# ESP32_Metal_Detector_v1_0.net
KiCad netlist of a schematic drawn in EAGLE
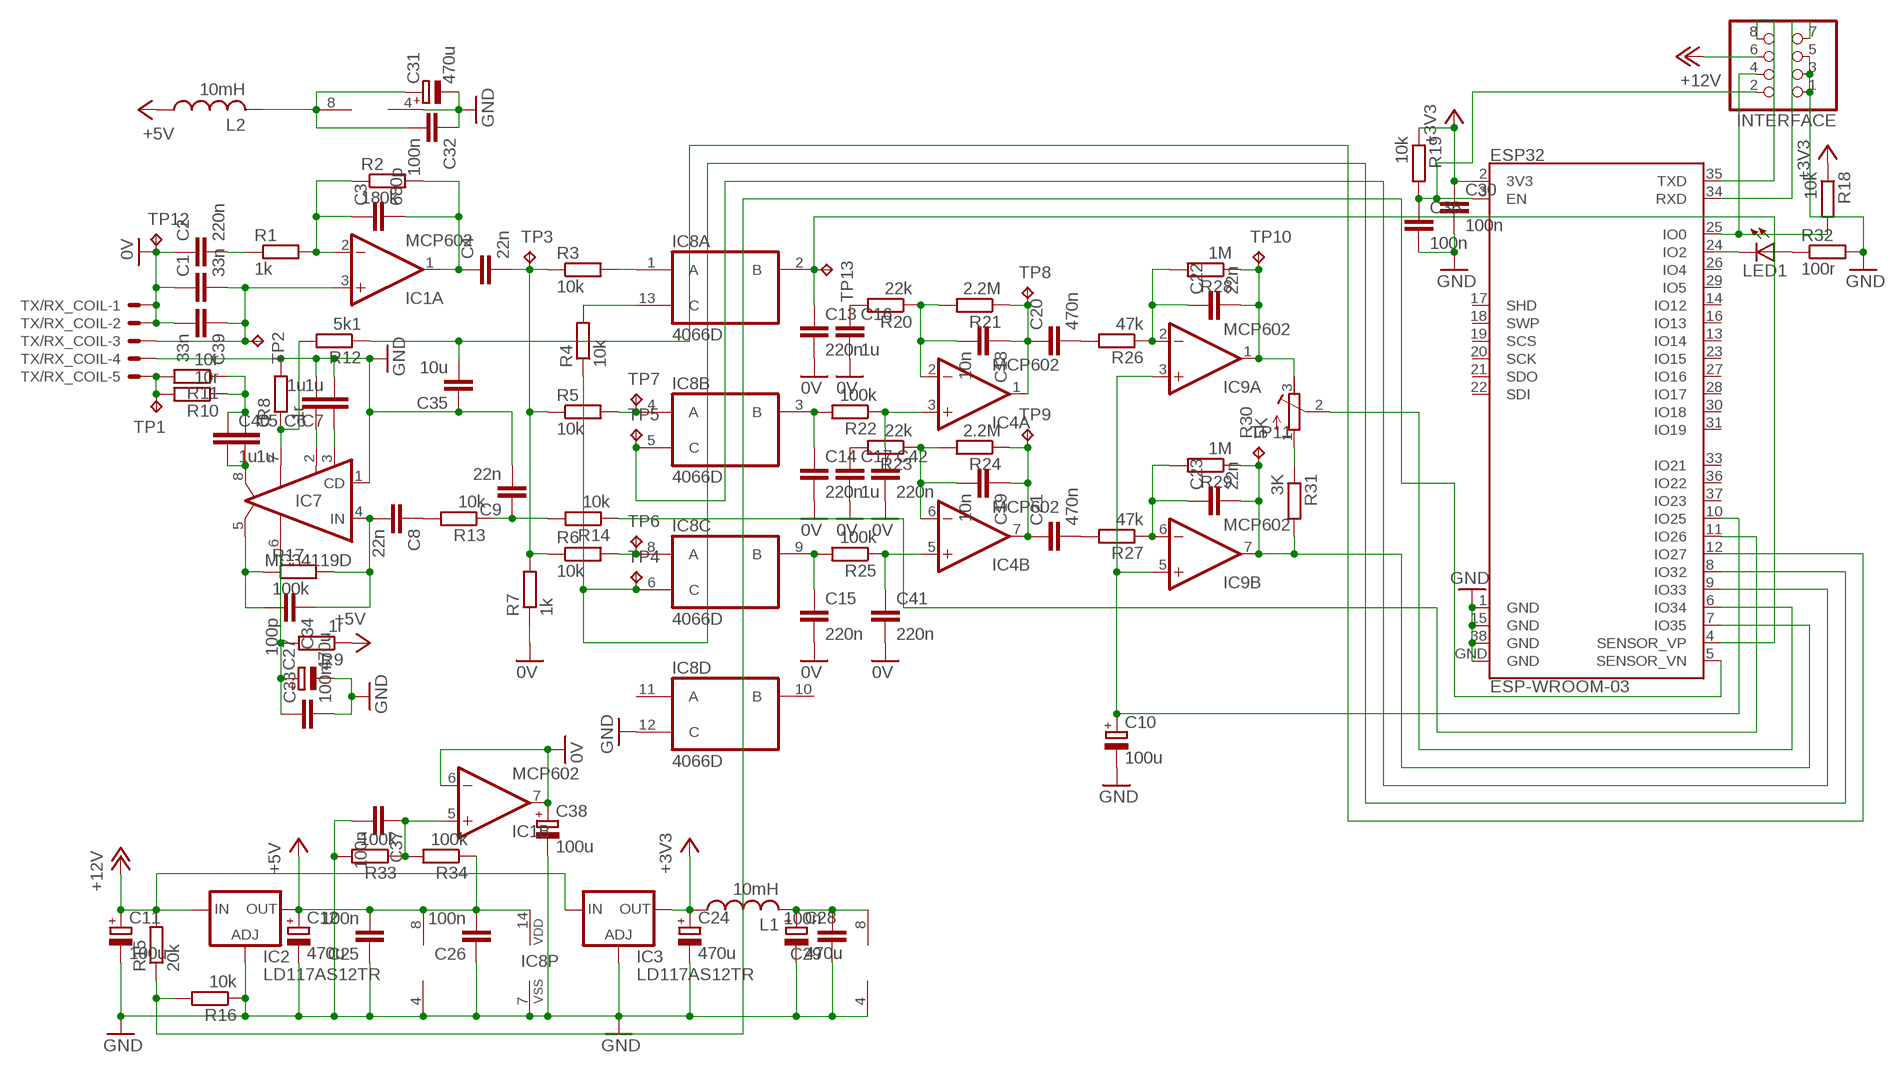
[diagram p0: schematic, sheet 1]

(export (version "E")
  (design (tool "Eeschema 10.0.6"))
  (components
    (comp (ref "C1")
      (value "33n")
      (footprint "eagle-import:C050-055X075")
      (libsource (lib "eagle-import") (part "C-EU050-055X075"))
    )
    (comp (ref "C2")
      (value "220n")
      (footprint "eagle-import:C1206")
      (libsource (lib "eagle-import") (part "resistor_C-EUC1206"))
    )
    (comp (ref "C3")
      (value "680p")
      (footprint "eagle-import:C1206")
      (libsource (lib "eagle-import") (part "resistor_C-EUC1206"))
    )
    (comp (ref "C4")
      (value "22n")
      (footprint "eagle-import:C1206")
      (libsource (lib "eagle-import") (part "resistor_C-EUC1206"))
    )
    (comp (ref "C5")
      (value "1u")
      (footprint "eagle-import:C050-055X075")
      (libsource (lib "eagle-import") (part "C-EU050-055X075"))
    )
    (comp (ref "C6")
      (value "1u")
      (footprint "eagle-import:C1206")
      (libsource (lib "eagle-import") (part "resistor_C-EUC1206"))
    )
    (comp (ref "C7")
      (value "1u")
      (footprint "eagle-import:C1206")
      (libsource (lib "eagle-import") (part "resistor_C-EUC1206"))
    )
    (comp (ref "C8")
      (value "22n")
      (footprint "eagle-import:C1206")
      (libsource (lib "eagle-import") (part "resistor_C-EUC1206"))
    )
    (comp (ref "C9")
      (value "22n")
      (footprint "eagle-import:C1206")
      (libsource (lib "eagle-import") (part "resistor_C-EUC1206"))
    )
    (comp (ref "C10")
      (value "100u")
      (footprint "eagle-import:SMC_B")
      (libsource (lib "eagle-import") (part "CPOL-EUSMCB"))
    )
    (comp (ref "C11")
      (value "100u")
      (footprint "eagle-import:SMC_E")
      (libsource (lib "eagle-import") (part "CPOL-EUSMCE"))
    )
    (comp (ref "C12")
      (value "470u")
      (footprint "eagle-import:SMC_D")
      (libsource (lib "eagle-import") (part "CPOL-EUSMCD"))
    )
    (comp (ref "C13")
      (value "220n")
      (footprint "eagle-import:C1206")
      (libsource (lib "eagle-import") (part "resistor_C-EUC1206"))
    )
    (comp (ref "C14")
      (value "220n")
      (footprint "eagle-import:C1206")
      (libsource (lib "eagle-import") (part "resistor_C-EUC1206"))
    )
    (comp (ref "C15")
      (value "220n")
      (footprint "eagle-import:C1206")
      (libsource (lib "eagle-import") (part "resistor_C-EUC1206"))
    )
    (comp (ref "C16")
      (value "1u")
      (footprint "eagle-import:C1206")
      (libsource (lib "eagle-import") (part "resistor_C-EUC1206"))
    )
    (comp (ref "C17")
      (value "1u")
      (footprint "eagle-import:C1206")
      (libsource (lib "eagle-import") (part "resistor_C-EUC1206"))
    )
    (comp (ref "C18")
      (value "10n")
      (footprint "eagle-import:C1206")
      (libsource (lib "eagle-import") (part "resistor_C-EUC1206"))
    )
    (comp (ref "C19")
      (value "10n")
      (footprint "eagle-import:C1206")
      (libsource (lib "eagle-import") (part "resistor_C-EUC1206"))
    )
    (comp (ref "C20")
      (value "470n")
      (footprint "eagle-import:C1206")
      (libsource (lib "eagle-import") (part "resistor_C-EUC1206"))
    )
    (comp (ref "C21")
      (value "470n")
      (footprint "eagle-import:C1206")
      (libsource (lib "eagle-import") (part "resistor_C-EUC1206"))
    )
    (comp (ref "C22")
      (value "22n")
      (footprint "eagle-import:C1206")
      (libsource (lib "eagle-import") (part "resistor_C-EUC1206"))
    )
    (comp (ref "C23")
      (value "22n")
      (footprint "eagle-import:C1206")
      (libsource (lib "eagle-import") (part "resistor_C-EUC1206"))
    )
    (comp (ref "C24")
      (value "470u")
      (footprint "eagle-import:SMC_D")
      (libsource (lib "eagle-import") (part "CPOL-EUSMCD"))
    )
    (comp (ref "C25")
      (value "100n")
      (footprint "eagle-import:C1206")
      (libsource (lib "eagle-import") (part "resistor_C-EUC1206"))
    )
    (comp (ref "C26")
      (value "100n")
      (footprint "eagle-import:C1206")
      (libsource (lib "eagle-import") (part "resistor_C-EUC1206"))
    )
    (comp (ref "C27")
      (value "470u")
      (footprint "eagle-import:SMC_D")
      (libsource (lib "eagle-import") (part "CPOL-EUSMCD"))
    )
    (comp (ref "C28")
      (value "470u")
      (footprint "eagle-import:SMC_D")
      (libsource (lib "eagle-import") (part "CPOL-EUSMCD"))
    )
    (comp (ref "C29")
      (value "100n")
      (footprint "eagle-import:C1206")
      (libsource (lib "eagle-import") (part "resistor_C-EUC1206"))
    )
    (comp (ref "C30")
      (value "100n")
      (footprint "eagle-import:C1206")
      (libsource (lib "eagle-import") (part "resistor_C-EUC1206"))
    )
    (comp (ref "C31")
      (value "470u")
      (footprint "eagle-import:SMC_D")
      (libsource (lib "eagle-import") (part "CPOL-EUSMCD"))
    )
    (comp (ref "C32")
      (value "100n")
      (footprint "eagle-import:C1206")
      (libsource (lib "eagle-import") (part "resistor_C-EUC1206"))
    )
    (comp (ref "C33")
      (value "100n")
      (footprint "eagle-import:C1206")
      (libsource (lib "eagle-import") (part "resistor_C-EUC1206"))
    )
    (comp (ref "C34")
      (value "100p")
      (footprint "eagle-import:C1206")
      (libsource (lib "eagle-import") (part "resistor_C-EUC1206"))
    )
    (comp (ref "C35")
      (value "10u")
      (footprint "eagle-import:C1206")
      (libsource (lib "eagle-import") (part "resistor_C-EUC1206"))
    )
    (comp (ref "C36")
      (value "100n")
      (footprint "eagle-import:C1206")
      (libsource (lib "eagle-import") (part "resistor_C-EUC1206"))
    )
    (comp (ref "C37")
      (value "100n")
      (footprint "eagle-import:C1206")
      (libsource (lib "eagle-import") (part "resistor_C-EUC1206"))
    )
    (comp (ref "C38")
      (value "100u")
      (footprint "eagle-import:SMC_B")
      (libsource (lib "eagle-import") (part "CPOL-EUSMCB"))
    )
    (comp (ref "C39")
      (value "33n")
      (footprint "eagle-import:C1206")
      (libsource (lib "eagle-import") (part "resistor_C-EUC1206"))
    )
    (comp (ref "C40")
      (value "1u")
      (footprint "eagle-import:C1206")
      (libsource (lib "eagle-import") (part "resistor_C-EUC1206"))
    )
    (comp (ref "C41")
      (value "220n")
      (footprint "eagle-import:C1206")
      (libsource (lib "eagle-import") (part "resistor_C-EUC1206"))
    )
    (comp (ref "C42")
      (value "220n")
      (footprint "eagle-import:C1206")
      (libsource (lib "eagle-import") (part "resistor_C-EUC1206"))
    )
    (comp (ref "ESP32")
      (value "ESP-WROOM-03")
      (footprint "eagle-import:ESP-WROOM-03")
      (libsource (lib "eagle-import") (part "ESP-WROOM-03"))
    )
    (comp (ref "IC1")
      (value "MCP602")
      (footprint "eagle-import:SO08")
      (libsource (lib "eagle-import") (part "LM393D"))
    )
    (comp (ref "IC2")
      (value "LD117AS12TR")
      (footprint "eagle-import:SOT223")
      (libsource (lib "eagle-import") (part "LD117A?S12TR"))
    )
    (comp (ref "IC3")
      (value "LD117AS12TR")
      (footprint "eagle-import:SOT223")
      (libsource (lib "eagle-import") (part "LD117A?S12TR"))
    )
    (comp (ref "IC4")
      (value "MCP602")
      (footprint "eagle-import:SO08")
      (libsource (lib "eagle-import") (part "LM393D"))
    )
    (comp (ref "IC7")
      (value "MC34119D")
      (footprint "eagle-import:SO08")
      (libsource (lib "eagle-import") (part "MC34119D"))
    )
    (comp (ref "IC8")
      (value "4066D")
      (footprint "eagle-import:SO14")
      (libsource (lib "eagle-import") (part "4066D"))
    )
    (comp (ref "IC9")
      (value "MCP602")
      (footprint "eagle-import:SO08")
      (libsource (lib "eagle-import") (part "LM393D"))
    )
    (comp (ref "INTERFACE")
      (value "PINHD-2X4")
      (footprint "eagle-import:2X04")
      (libsource (lib "eagle-import") (part "PINHD-2X4"))
    )
    (comp (ref "L1")
      (value "10mH")
      (footprint "eagle-import:L5650M")
      (libsource (lib "eagle-import") (part "L-USL5650M"))
    )
    (comp (ref "L2")
      (value "10mH")
      (footprint "eagle-import:L5650M")
      (libsource (lib "eagle-import") (part "L-USL5650M"))
    )
    (comp (ref "LED1")
      (value "LEDSML1206")
      (footprint "eagle-import:SML1206")
      (libsource (lib "eagle-import") (part "LEDSML1206"))
    )
    (comp (ref "R1")
      (value "1k")
      (footprint "eagle-import:R1206")
      (libsource (lib "eagle-import") (part "R-EU_R1206"))
    )
    (comp (ref "R2")
      (value "180k")
      (footprint "eagle-import:R1206")
      (libsource (lib "eagle-import") (part "R-EU_R1206"))
    )
    (comp (ref "R3")
      (value "10k")
      (footprint "eagle-import:R1206")
      (libsource (lib "eagle-import") (part "R-EU_R1206"))
    )
    (comp (ref "R4")
      (value "10k")
      (footprint "eagle-import:R1206")
      (libsource (lib "eagle-import") (part "R-EU_R1206"))
    )
    (comp (ref "R5")
      (value "10k")
      (footprint "eagle-import:R1206")
      (libsource (lib "eagle-import") (part "R-EU_R1206"))
    )
    (comp (ref "R6")
      (value "10k")
      (footprint "eagle-import:R1206")
      (libsource (lib "eagle-import") (part "R-EU_R1206"))
    )
    (comp (ref "R7")
      (value "1k")
      (footprint "eagle-import:R1206")
      (libsource (lib "eagle-import") (part "R-EU_R1206"))
    )
    (comp (ref "R8")
      (value "1r")
      (footprint "eagle-import:R1206")
      (libsource (lib "eagle-import") (part "R-EU_R1206"))
    )
    (comp (ref "R9")
      (value "1r")
      (footprint "eagle-import:R1206")
      (libsource (lib "eagle-import") (part "R-EU_R1206"))
    )
    (comp (ref "R10")
      (value "10r")
      (footprint "eagle-import:R1206")
      (libsource (lib "eagle-import") (part "R-EU_R1206"))
    )
    (comp (ref "R11")
      (value "10r")
      (footprint "eagle-import:R1206")
      (libsource (lib "eagle-import") (part "R-EU_R1206"))
    )
    (comp (ref "R12")
      (value "5k1")
      (footprint "eagle-import:R1206")
      (libsource (lib "eagle-import") (part "R-EU_R1206"))
    )
    (comp (ref "R13")
      (value "10k")
      (footprint "eagle-import:R1206")
      (libsource (lib "eagle-import") (part "R-EU_R1206"))
    )
    (comp (ref "R14")
      (value "10k")
      (footprint "eagle-import:R1206")
      (libsource (lib "eagle-import") (part "R-EU_R1206"))
    )
    (comp (ref "R15")
      (value "20k")
      (footprint "eagle-import:R1206")
      (libsource (lib "eagle-import") (part "R-EU_R1206"))
    )
    (comp (ref "R16")
      (value "10k")
      (footprint "eagle-import:R1206")
      (libsource (lib "eagle-import") (part "R-EU_R1206"))
    )
    (comp (ref "R17")
      (value "100k")
      (footprint "eagle-import:R1206")
      (libsource (lib "eagle-import") (part "R-EU_R1206"))
    )
    (comp (ref "R18")
      (value "10k")
      (footprint "eagle-import:R1206")
      (libsource (lib "eagle-import") (part "R-EU_R1206"))
    )
    (comp (ref "R19")
      (value "10k")
      (footprint "eagle-import:R1206")
      (libsource (lib "eagle-import") (part "R-EU_R1206"))
    )
    (comp (ref "R20")
      (value "22k")
      (footprint "eagle-import:R1206")
      (libsource (lib "eagle-import") (part "R-EU_R1206"))
    )
    (comp (ref "R21")
      (value "2.2M")
      (footprint "eagle-import:R1206")
      (libsource (lib "eagle-import") (part "R-EU_R1206"))
    )
    (comp (ref "R22")
      (value "100k")
      (footprint "eagle-import:R1206")
      (libsource (lib "eagle-import") (part "R-EU_R1206"))
    )
    (comp (ref "R23")
      (value "22k")
      (footprint "eagle-import:R1206")
      (libsource (lib "eagle-import") (part "R-EU_R1206"))
    )
    (comp (ref "R24")
      (value "2.2M")
      (footprint "eagle-import:R1206")
      (libsource (lib "eagle-import") (part "R-EU_R1206"))
    )
    (comp (ref "R25")
      (value "100k")
      (footprint "eagle-import:R1206")
      (libsource (lib "eagle-import") (part "R-EU_R1206"))
    )
    (comp (ref "R26")
      (value "47k")
      (footprint "eagle-import:R1206")
      (libsource (lib "eagle-import") (part "R-EU_R1206"))
    )
    (comp (ref "R27")
      (value "47k")
      (footprint "eagle-import:R1206")
      (libsource (lib "eagle-import") (part "R-EU_R1206"))
    )
    (comp (ref "R28")
      (value "1M")
      (footprint "eagle-import:R1206")
      (libsource (lib "eagle-import") (part "R-EU_R1206"))
    )
    (comp (ref "R29")
      (value "1M")
      (footprint "eagle-import:R1206")
      (libsource (lib "eagle-import") (part "R-EU_R1206"))
    )
    (comp (ref "R30")
      (value "5K")
      (footprint "eagle-import:RTRIM4G_J")
      (libsource (lib "eagle-import") (part "R-TRIMM4G/J"))
    )
    (comp (ref "R31")
      (value "3K")
      (footprint "eagle-import:R1206")
      (libsource (lib "eagle-import") (part "R-EU_R1206"))
    )
    (comp (ref "R32")
      (value "100r")
      (footprint "eagle-import:R1206")
      (libsource (lib "eagle-import") (part "R-EU_R1206"))
    )
    (comp (ref "R33")
      (value "100k")
      (footprint "eagle-import:R1206")
      (libsource (lib "eagle-import") (part "R-EU_R1206"))
    )
    (comp (ref "R34")
      (value "100k")
      (footprint "eagle-import:R1206")
      (libsource (lib "eagle-import") (part "R-EU_R1206"))
    )
    (comp (ref "TP1")
      (value "TPPAD1-13")
      (footprint "eagle-import:P1-13")
      (libsource (lib "eagle-import") (part "TPPAD1-13"))
    )
    (comp (ref "TP2")
      (value "TPPAD1-13")
      (footprint "eagle-import:P1-13")
      (libsource (lib "eagle-import") (part "TPPAD1-13"))
    )
    (comp (ref "TP3")
      (value "TPPAD1-13")
      (footprint "eagle-import:P1-13")
      (libsource (lib "eagle-import") (part "TPPAD1-13"))
    )
    (comp (ref "TP4")
      (value "TPPAD1-13")
      (footprint "eagle-import:P1-13")
      (libsource (lib "eagle-import") (part "TPPAD1-13"))
    )
    (comp (ref "TP5")
      (value "TPPAD1-13")
      (footprint "eagle-import:P1-13")
      (libsource (lib "eagle-import") (part "TPPAD1-13"))
    )
    (comp (ref "TP6")
      (value "TPPAD1-13")
      (footprint "eagle-import:P1-13")
      (libsource (lib "eagle-import") (part "TPPAD1-13"))
    )
    (comp (ref "TP7")
      (value "TPPAD1-13")
      (footprint "eagle-import:P1-13")
      (libsource (lib "eagle-import") (part "TPPAD1-13"))
    )
    (comp (ref "TP8")
      (value "TPPAD1-13")
      (footprint "eagle-import:P1-13")
      (libsource (lib "eagle-import") (part "TPPAD1-13"))
    )
    (comp (ref "TP9")
      (value "TPPAD1-13")
      (footprint "eagle-import:P1-13")
      (libsource (lib "eagle-import") (part "TPPAD1-13"))
    )
    (comp (ref "TP10")
      (value "TPPAD1-13")
      (footprint "eagle-import:P1-13")
      (libsource (lib "eagle-import") (part "TPPAD1-13"))
    )
    (comp (ref "TP11")
      (value "TPPAD1-13")
      (footprint "eagle-import:P1-13")
      (libsource (lib "eagle-import") (part "TPPAD1-13"))
    )
    (comp (ref "TP12")
      (value "TPPAD1-13")
      (footprint "eagle-import:P1-13")
      (libsource (lib "eagle-import") (part "TPPAD1-13"))
    )
    (comp (ref "TP13")
      (value "TPPAD1-13")
      (footprint "eagle-import:P1-13")
      (libsource (lib "eagle-import") (part "TPPAD1-13"))
    )
    (comp (ref "TX/RX_COIL")
      (value "22-23-2051")
      (footprint "eagle-import:22-23-2051")
      (fields (field (name "MF") "MOLEX"))
      (libsource (lib "eagle-import") (part "22-23-2051"))
    )
  )
  (nets
    (net (code "1") (name "+3V3") (class "Default")
      (node (ref "C24") (pin "+") (pinfunction "+_+") (pintype "passive"))
      (node (ref "C30") (pin "1") (pinfunction "1_1") (pintype "passive"))
      (node (ref "ESP32") (pin "2") (pinfunction "3V3_2") (pintype "bidirectional"))
      (node (ref "IC3") (pin "4") (pinfunction "OUT_4") (pintype "passive"))
      (node (ref "L1") (pin "1") (pinfunction "1_1") (pintype "passive"))
      (node (ref "R18") (pin "1") (pinfunction "1_1") (pintype "passive"))
      (node (ref "R19") (pin "1") (pinfunction "1_1") (pintype "passive"))
    )
    (net (code "2") (name "+5V") (class "Default")
      (node (ref "C12") (pin "+") (pinfunction "+_+") (pintype "passive"))
      (node (ref "C25") (pin "2") (pinfunction "2_2") (pintype "passive"))
      (node (ref "C26") (pin "2") (pinfunction "2_2") (pintype "passive"))
      (node (ref "IC2") (pin "4") (pinfunction "OUT_4") (pintype "passive"))
      (node (ref "IC4") (pin "8") (pinfunction "V+_8") (pintype "power_in"))
      (node (ref "IC8") (pin "14") (pinfunction "VDD_14") (pintype "power_in"))
      (node (ref "L2") (pin "1") (pinfunction "1_1") (pintype "passive"))
      (node (ref "R34") (pin "1") (pinfunction "1_1") (pintype "passive"))
      (node (ref "R9") (pin "1") (pinfunction "1_1") (pintype "passive"))
    )
    (net (code "3") (name "+12V") (class "Default")
      (node (ref "C11") (pin "+") (pinfunction "+_+") (pintype "passive"))
      (node (ref "IC2") (pin "3") (pinfunction "IN_3") (pintype "input"))
      (node (ref "IC3") (pin "3") (pinfunction "IN_3") (pintype "input"))
      (node (ref "INTERFACE") (pin "6") (pinfunction "6_6") (pintype "passive"))
      (node (ref "R15") (pin "2") (pinfunction "2_2") (pintype "passive"))
    )
    (net (code "4") (name "0V") (class "Default")
      (node (ref "C1") (pin "1") (pinfunction "1_1") (pintype "passive"))
      (node (ref "C13") (pin "2") (pinfunction "2_2") (pintype "passive"))
      (node (ref "C14") (pin "2") (pinfunction "2_2") (pintype "passive"))
      (node (ref "C15") (pin "2") (pinfunction "2_2") (pintype "passive"))
      (node (ref "C16") (pin "2") (pinfunction "2_2") (pintype "passive"))
      (node (ref "C17") (pin "2") (pinfunction "2_2") (pintype "passive"))
      (node (ref "C2") (pin "1") (pinfunction "1_1") (pintype "passive"))
      (node (ref "C38") (pin "+") (pinfunction "+_+") (pintype "passive"))
      (node (ref "C39") (pin "2") (pinfunction "2_2") (pintype "passive"))
      (node (ref "C41") (pin "2") (pinfunction "2_2") (pintype "passive"))
      (node (ref "C42") (pin "2") (pinfunction "2_2") (pintype "passive"))
      (node (ref "IC1") (pin "6") (pinfunction "-IN_6") (pintype "input"))
      (node (ref "IC1") (pin "7") (pinfunction "OUT_7") (pintype "output"))
      (node (ref "R7") (pin "1") (pinfunction "1_1") (pintype "passive"))
      (node (ref "TP12") (pin "TP") (pinfunction "TP_TP") (pintype "input"))
      (node (ref "TX/RX_COIL") (pin "1") (pinfunction "S_1") (pintype "passive"))
      (node (ref "TX/RX_COIL") (pin "2") (pinfunction "S_2") (pintype "passive"))
    )
    (net (code "5") (name "GND") (class "Default")
      (node (ref "C10") (pin "-") (pinfunction "-_-") (pintype "passive"))
      (node (ref "C11") (pin "-") (pinfunction "-_-") (pintype "passive"))
      (node (ref "C12") (pin "-") (pinfunction "-_-") (pintype "passive"))
      (node (ref "C24") (pin "-") (pinfunction "-_-") (pintype "passive"))
      (node (ref "C25") (pin "1") (pinfunction "1_1") (pintype "passive"))
      (node (ref "C26") (pin "1") (pinfunction "1_1") (pintype "passive"))
      (node (ref "C27") (pin "-") (pinfunction "-_-") (pintype "passive"))
      (node (ref "C28") (pin "-") (pinfunction "-_-") (pintype "passive"))
      (node (ref "C29") (pin "1") (pinfunction "1_1") (pintype "passive"))
      (node (ref "C30") (pin "2") (pinfunction "2_2") (pintype "passive"))
      (node (ref "C31") (pin "-") (pinfunction "-_-") (pintype "passive"))
      (node (ref "C32") (pin "1") (pinfunction "1_1") (pintype "passive"))
      (node (ref "C33") (pin "2") (pinfunction "2_2") (pintype "passive"))
      (node (ref "C35") (pin "1") (pinfunction "1_1") (pintype "passive"))
      (node (ref "C36") (pin "2") (pinfunction "2_2") (pintype "passive"))
      (node (ref "C37") (pin "2") (pinfunction "2_2") (pintype "passive"))
      (node (ref "C38") (pin "-") (pinfunction "-_-") (pintype "passive"))
      (node (ref "C6") (pin "2") (pinfunction "2_2") (pintype "passive"))
      (node (ref "C7") (pin "2") (pinfunction "2_2") (pintype "passive"))
      (node (ref "C9") (pin "2") (pinfunction "2_2") (pintype "passive"))
      (node (ref "ESP32") (pin "1") (pinfunction "GND_1") (pintype "bidirectional"))
      (node (ref "ESP32") (pin "15") (pinfunction "GND_15") (pintype "bidirectional"))
      (node (ref "ESP32") (pin "38") (pinfunction "GND_38") (pintype "bidirectional"))
      (node (ref "ESP32") (pin "GND") (pinfunction "GND_GND") (pintype "bidirectional"))
      (node (ref "IC1") (pin "4") (pinfunction "V-_4") (pintype "power_in"))
      (node (ref "IC2") (pin "1") (pinfunction "ADJ_1") (pintype "input"))
      (node (ref "IC3") (pin "1") (pinfunction "ADJ_1") (pintype "input"))
      (node (ref "IC4") (pin "4") (pinfunction "V-_4") (pintype "power_in"))
      (node (ref "IC7") (pin "1") (pinfunction "CD_1") (pintype "passive"))
      (node (ref "IC8") (pin "12") (pinfunction "C_12") (pintype "input"))
      (node (ref "IC8") (pin "7") (pinfunction "VSS_7") (pintype "power_in"))
      (node (ref "IC9") (pin "4") (pinfunction "V-_4") (pintype "power_in"))
      (node (ref "INTERFACE") (pin "1") (pinfunction "1_1") (pintype "passive"))
      (node (ref "INTERFACE") (pin "3") (pinfunction "3_3") (pintype "passive"))
      (node (ref "INTERFACE") (pin "5") (pinfunction "5_5") (pintype "passive"))
      (node (ref "R16") (pin "1") (pinfunction "1_1") (pintype "passive"))
      (node (ref "R32") (pin "2") (pinfunction "2_2") (pintype "passive"))
      (node (ref "R33") (pin "2") (pinfunction "2_2") (pintype "passive"))
      (node (ref "R8") (pin "2") (pinfunction "2_2") (pintype "passive"))
      (node (ref "TX/RX_COIL") (pin "4") (pinfunction "S_4") (pintype "passive"))
    )
    (net (code "6") (name "Net-(C2-Pad2)") (class "Default")
      (node (ref "C2") (pin "2") (pinfunction "2_2") (pintype "passive"))
      (node (ref "R1") (pin "1") (pinfunction "1_1") (pintype "passive"))
    )
    (net (code "7") (name "Net-(C4-Pad2)") (class "Default")
      (node (ref "C4") (pin "2") (pinfunction "2_2") (pintype "passive"))
      (node (ref "R3") (pin "1") (pinfunction "1_1") (pintype "passive"))
      (node (ref "R5") (pin "1") (pinfunction "1_1") (pintype "passive"))
      (node (ref "R6") (pin "1") (pinfunction "1_1") (pintype "passive"))
      (node (ref "R7") (pin "2") (pinfunction "2_2") (pintype "passive"))
      (node (ref "TP3") (pin "TP") (pinfunction "TP_TP") (pintype "input"))
    )
    (net (code "8") (name "Net-(C8-Pad1)") (class "Default")
      (node (ref "C8") (pin "1") (pinfunction "1_1") (pintype "passive"))
      (node (ref "R13") (pin "2") (pinfunction "2_2") (pintype "passive"))
    )
    (net (code "9") (name "Net-(C9-Pad1)") (class "Default")
      (node (ref "C9") (pin "1") (pinfunction "1_1") (pintype "passive"))
      (node (ref "R13") (pin "1") (pinfunction "1_1") (pintype "passive"))
      (node (ref "R14") (pin "2") (pinfunction "2_2") (pintype "passive"))
    )
    (net (code "10") (name "Net-(C16-Pad1)") (class "Default")
      (node (ref "C16") (pin "1") (pinfunction "1_1") (pintype "passive"))
      (node (ref "R20") (pin "2") (pinfunction "2_2") (pintype "passive"))
    )
    (net (code "11") (name "Net-(C17-Pad1)") (class "Default")
      (node (ref "C17") (pin "1") (pinfunction "1_1") (pintype "passive"))
      (node (ref "R23") (pin "2") (pinfunction "2_2") (pintype "passive"))
    )
    (net (code "12") (name "Net-(C20-Pad2)") (class "Default")
      (node (ref "C20") (pin "2") (pinfunction "2_2") (pintype "passive"))
      (node (ref "R26") (pin "2") (pinfunction "2_2") (pintype "passive"))
    )
    (net (code "13") (name "Net-(C21-Pad2)") (class "Default")
      (node (ref "C21") (pin "2") (pinfunction "2_2") (pintype "passive"))
      (node (ref "R27") (pin "2") (pinfunction "2_2") (pintype "passive"))
    )
    (net (code "14") (name "Net-(C40-Pad1)") (class "Default")
      (node (ref "C40") (pin "1") (pinfunction "1_1") (pintype "passive"))
      (node (ref "C5") (pin "1") (pinfunction "1_1") (pintype "passive"))
      (node (ref "R10") (pin "1") (pinfunction "1_1") (pintype "passive"))
      (node (ref "R11") (pin "1") (pinfunction "1_1") (pintype "passive"))
    )
    (net (code "15") (name "Net-(ESP32-EN)") (class "Default")
      (node (ref "C36") (pin "1") (pinfunction "1_1") (pintype "passive"))
      (node (ref "ESP32") (pin "3") (pinfunction "EN_3") (pintype "bidirectional"))
      (node (ref "INTERFACE") (pin "2") (pinfunction "2_2") (pintype "passive"))
      (node (ref "R19") (pin "2") (pinfunction "2_2") (pintype "passive"))
    )
    (net (code "16") (name "Net-(ESP32-IO0)") (class "Default")
      (node (ref "ESP32") (pin "25") (pinfunction "IO0_25") (pintype "bidirectional"))
      (node (ref "INTERFACE") (pin "4") (pinfunction "4_4") (pintype "passive"))
      (node (ref "R18") (pin "2") (pinfunction "2_2") (pintype "passive"))
    )
    (net (code "17") (name "Net-(ESP32-IO2)") (class "Default")
      (node (ref "ESP32") (pin "24") (pinfunction "IO2_24") (pintype "bidirectional"))
      (node (ref "LED1") (pin "C") (pinfunction "C_C") (pintype "passive"))
    )
    (net (code "18") (name "Net-(ESP32-IO25)") (class "Default")
      (node (ref "C10") (pin "+") (pinfunction "+_+") (pintype "passive"))
      (node (ref "ESP32") (pin "10") (pinfunction "IO25_10") (pintype "bidirectional"))
      (node (ref "IC9") (pin "3") (pinfunction "+IN_3") (pintype "input"))
      (node (ref "IC9") (pin "5") (pinfunction "+IN_5") (pintype "input"))
    )
    (net (code "19") (name "Net-(ESP32-IO26)") (class "Default")
      (node (ref "ESP32") (pin "11") (pinfunction "IO26_11") (pintype "bidirectional"))
      (node (ref "R14") (pin "1") (pinfunction "1_1") (pintype "passive"))
    )
    (net (code "20") (name "Net-(ESP32-IO27)") (class "Default")
      (node (ref "C35") (pin "2") (pinfunction "2_2") (pintype "passive"))
      (node (ref "ESP32") (pin "12") (pinfunction "IO27_12") (pintype "bidirectional"))
      (node (ref "R12") (pin "1") (pinfunction "1_1") (pintype "passive"))
    )
    (net (code "21") (name "Net-(ESP32-IO32)") (class "Default")
      (node (ref "ESP32") (pin "8") (pinfunction "IO32_8") (pintype "bidirectional"))
      (node (ref "IC8") (pin "6") (pinfunction "C_6") (pintype "input"))
      (node (ref "R4") (pin "1") (pinfunction "1_1") (pintype "passive"))
      (node (ref "TP4") (pin "TP") (pinfunction "TP_TP") (pintype "input"))
    )
    (net (code "22") (name "Net-(ESP32-IO33)") (class "Default")
      (node (ref "ESP32") (pin "9") (pinfunction "IO33_9") (pintype "bidirectional"))
      (node (ref "IC8") (pin "5") (pinfunction "C_5") (pintype "input"))
      (node (ref "TP5") (pin "TP") (pinfunction "TP_TP") (pintype "input"))
    )
    (net (code "23") (name "Net-(ESP32-IO34)") (class "Default")
      (node (ref "ESP32") (pin "6") (pinfunction "IO34_6") (pintype "bidirectional"))
      (node (ref "R30") (pin "2") (pinfunction "S_2") (pintype "passive"))
    )
    (net (code "24") (name "Net-(ESP32-IO35)") (class "Default")
      (node (ref "C23") (pin "2") (pinfunction "2_2") (pintype "passive"))
      (node (ref "ESP32") (pin "7") (pinfunction "IO35_7") (pintype "bidirectional"))
      (node (ref "IC9") (pin "7") (pinfunction "OUT_7") (pintype "output"))
      (node (ref "R29") (pin "1") (pinfunction "1_1") (pintype "passive"))
      (node (ref "R31") (pin "2") (pinfunction "2_2") (pintype "passive"))
      (node (ref "TP11") (pin "TP") (pinfunction "TP_TP") (pintype "input"))
    )
    (net (code "25") (name "Net-(ESP32-RXD)") (class "Default")
      (node (ref "ESP32") (pin "34") (pinfunction "RXD_34") (pintype "bidirectional"))
      (node (ref "INTERFACE") (pin "7") (pinfunction "7_7") (pintype "passive"))
    )
    (net (code "26") (name "Net-(ESP32-SENSOR_VN)") (class "Default")
      (node (ref "ESP32") (pin "5") (pinfunction "SENSOR_VN_5") (pintype "bidirectional"))
      (node (ref "R15") (pin "1") (pinfunction "1_1") (pintype "passive"))
      (node (ref "R16") (pin "2") (pinfunction "2_2") (pintype "passive"))
    )
    (net (code "27") (name "Net-(ESP32-SENSOR_VP)") (class "Default")
      (node (ref "C13") (pin "1") (pinfunction "1_1") (pintype "passive"))
      (node (ref "ESP32") (pin "4") (pinfunction "SENSOR_VP_4") (pintype "bidirectional"))
      (node (ref "IC8") (pin "2") (pinfunction "B_2") (pintype "tri_state"))
      (node (ref "TP13") (pin "TP") (pinfunction "TP_TP") (pintype "input"))
    )
    (net (code "28") (name "Net-(ESP32-TXD)") (class "Default")
      (node (ref "ESP32") (pin "35") (pinfunction "TXD_35") (pintype "bidirectional"))
      (node (ref "INTERFACE") (pin "8") (pinfunction "8_8") (pintype "passive"))
    )
    (net (code "29") (name "Net-(IC1A-+IN)") (class "Default")
      (node (ref "C1") (pin "2") (pinfunction "2_2") (pintype "passive"))
      (node (ref "C39") (pin "1") (pinfunction "1_1") (pintype "passive"))
      (node (ref "IC1") (pin "3") (pinfunction "+IN_3") (pintype "input"))
      (node (ref "TP2") (pin "TP") (pinfunction "TP_TP") (pintype "input"))
      (node (ref "TX/RX_COIL") (pin "3") (pinfunction "S_3") (pintype "passive"))
    )
    (net (code "30") (name "Net-(IC1A--IN)") (class "Default")
      (node (ref "C3") (pin "1") (pinfunction "1_1") (pintype "passive"))
      (node (ref "IC1") (pin "2") (pinfunction "-IN_2") (pintype "input"))
      (node (ref "R1") (pin "2") (pinfunction "2_2") (pintype "passive"))
      (node (ref "R2") (pin "1") (pinfunction "1_1") (pintype "passive"))
    )
    (net (code "31") (name "Net-(IC1A-OUT)") (class "Default")
      (node (ref "C3") (pin "2") (pinfunction "2_2") (pintype "passive"))
      (node (ref "C4") (pin "1") (pinfunction "1_1") (pintype "passive"))
      (node (ref "IC1") (pin "1") (pinfunction "OUT_1") (pintype "output"))
      (node (ref "R2") (pin "2") (pinfunction "2_2") (pintype "passive"))
    )
    (net (code "32") (name "Net-(IC1B-+IN)") (class "Default")
      (node (ref "C37") (pin "1") (pinfunction "1_1") (pintype "passive"))
      (node (ref "IC1") (pin "5") (pinfunction "+IN_5") (pintype "input"))
      (node (ref "R33") (pin "1") (pinfunction "1_1") (pintype "passive"))
      (node (ref "R34") (pin "2") (pinfunction "2_2") (pintype "passive"))
    )
    (net (code "33") (name "Net-(IC1C-V+)") (class "Default")
      (node (ref "C31") (pin "+") (pinfunction "+_+") (pintype "passive"))
      (node (ref "C32") (pin "2") (pinfunction "2_2") (pintype "passive"))
      (node (ref "IC1") (pin "8") (pinfunction "V+_8") (pintype "power_in"))
      (node (ref "L2") (pin "2") (pinfunction "2_2") (pintype "passive"))
    )
    (net (code "34") (name "Net-(IC4A-+IN)") (class "Default")
      (node (ref "C42") (pin "1") (pinfunction "1_1") (pintype "passive"))
      (node (ref "IC4") (pin "3") (pinfunction "+IN_3") (pintype "input"))
      (node (ref "R22") (pin "1") (pinfunction "1_1") (pintype "passive"))
    )
    (net (code "35") (name "Net-(IC4A--IN)") (class "Default")
      (node (ref "C18") (pin "2") (pinfunction "2_2") (pintype "passive"))
      (node (ref "IC4") (pin "2") (pinfunction "-IN_2") (pintype "input"))
      (node (ref "R20") (pin "1") (pinfunction "1_1") (pintype "passive"))
      (node (ref "R21") (pin "2") (pinfunction "2_2") (pintype "passive"))
    )
    (net (code "36") (name "Net-(IC4A-OUT)") (class "Default")
      (node (ref "C18") (pin "1") (pinfunction "1_1") (pintype "passive"))
      (node (ref "C20") (pin "1") (pinfunction "1_1") (pintype "passive"))
      (node (ref "IC4") (pin "1") (pinfunction "OUT_1") (pintype "output"))
      (node (ref "R21") (pin "1") (pinfunction "1_1") (pintype "passive"))
      (node (ref "TP8") (pin "TP") (pinfunction "TP_TP") (pintype "input"))
    )
    (net (code "37") (name "Net-(IC4B-+IN)") (class "Default")
      (node (ref "C41") (pin "1") (pinfunction "1_1") (pintype "passive"))
      (node (ref "IC4") (pin "5") (pinfunction "+IN_5") (pintype "input"))
      (node (ref "R25") (pin "1") (pinfunction "1_1") (pintype "passive"))
    )
    (net (code "38") (name "Net-(IC4B--IN)") (class "Default")
      (node (ref "C19") (pin "2") (pinfunction "2_2") (pintype "passive"))
      (node (ref "IC4") (pin "6") (pinfunction "-IN_6") (pintype "input"))
      (node (ref "R23") (pin "1") (pinfunction "1_1") (pintype "passive"))
      (node (ref "R24") (pin "2") (pinfunction "2_2") (pintype "passive"))
    )
    (net (code "39") (name "Net-(IC4B-OUT)") (class "Default")
      (node (ref "C19") (pin "1") (pinfunction "1_1") (pintype "passive"))
      (node (ref "C21") (pin "1") (pinfunction "1_1") (pintype "passive"))
      (node (ref "IC4") (pin "7") (pinfunction "OUT_7") (pintype "output"))
      (node (ref "R24") (pin "1") (pinfunction "1_1") (pintype "passive"))
      (node (ref "TP9") (pin "TP") (pinfunction "TP_TP") (pintype "input"))
    )
    (net (code "40") (name "Net-(IC7-FC1)") (class "Default")
      (node (ref "C7") (pin "1") (pinfunction "1_1") (pintype "passive"))
      (node (ref "IC7") (pin "3") (pinfunction "FC1_3") (pintype "passive"))
    )
    (net (code "41") (name "Net-(IC7-FC2)") (class "Default")
      (node (ref "C6") (pin "1") (pinfunction "1_1") (pintype "passive"))
      (node (ref "IC7") (pin "2") (pinfunction "FC2_2") (pintype "passive"))
    )
    (net (code "42") (name "Net-(IC7-GND)") (class "Default")
      (node (ref "IC7") (pin "7") (pinfunction "GND_7") (pintype "power_in"))
      (node (ref "R12") (pin "2") (pinfunction "2_2") (pintype "passive"))
      (node (ref "R8") (pin "1") (pinfunction "1_1") (pintype "passive"))
    )
    (net (code "43") (name "Net-(IC7-IN)") (class "Default")
      (node (ref "C34") (pin "1") (pinfunction "1_1") (pintype "passive"))
      (node (ref "C8") (pin "2") (pinfunction "2_2") (pintype "passive"))
      (node (ref "IC7") (pin "4") (pinfunction "IN_4") (pintype "input"))
      (node (ref "R17") (pin "2") (pinfunction "2_2") (pintype "passive"))
    )
    (net (code "44") (name "Net-(IC7-VCC)") (class "Default")
      (node (ref "C27") (pin "+") (pinfunction "+_+") (pintype "passive"))
      (node (ref "C33") (pin "1") (pinfunction "1_1") (pintype "passive"))
      (node (ref "IC7") (pin "6") (pinfunction "VCC_6") (pintype "power_in"))
      (node (ref "R9") (pin "2") (pinfunction "2_2") (pintype "passive"))
    )
    (net (code "45") (name "Net-(IC7-VO1)") (class "Default")
      (node (ref "C34") (pin "2") (pinfunction "2_2") (pintype "passive"))
      (node (ref "IC7") (pin "5") (pinfunction "VO1_5") (pintype "output"))
      (node (ref "R17") (pin "1") (pinfunction "1_1") (pintype "passive"))
    )
    (net (code "46") (name "Net-(IC7-VO2)") (class "Default")
      (node (ref "C40") (pin "2") (pinfunction "2_2") (pintype "passive"))
      (node (ref "C5") (pin "2") (pinfunction "2_2") (pintype "passive"))
      (node (ref "IC7") (pin "8") (pinfunction "VO2_8") (pintype "output"))
    )
    (net (code "47") (name "Net-(IC8A-A)") (class "Default")
      (node (ref "IC8") (pin "1") (pinfunction "A_1") (pintype "tri_state"))
      (node (ref "R3") (pin "2") (pinfunction "2_2") (pintype "passive"))
    )
    (net (code "48") (name "Net-(IC8A-C)") (class "Default")
      (node (ref "IC8") (pin "13") (pinfunction "C_13") (pintype "input"))
      (node (ref "R4") (pin "2") (pinfunction "2_2") (pintype "passive"))
    )
    (net (code "49") (name "Net-(IC8B-A)") (class "Default")
      (node (ref "IC8") (pin "4") (pinfunction "A_4") (pintype "tri_state"))
      (node (ref "R5") (pin "2") (pinfunction "2_2") (pintype "passive"))
      (node (ref "TP7") (pin "TP") (pinfunction "TP_TP") (pintype "input"))
    )
    (net (code "50") (name "Net-(IC8B-B)") (class "Default")
      (node (ref "C14") (pin "1") (pinfunction "1_1") (pintype "passive"))
      (node (ref "IC8") (pin "3") (pinfunction "B_3") (pintype "tri_state"))
      (node (ref "R22") (pin "2") (pinfunction "2_2") (pintype "passive"))
    )
    (net (code "51") (name "Net-(IC8C-A)") (class "Default")
      (node (ref "IC8") (pin "8") (pinfunction "A_8") (pintype "tri_state"))
      (node (ref "R6") (pin "2") (pinfunction "2_2") (pintype "passive"))
      (node (ref "TP6") (pin "TP") (pinfunction "TP_TP") (pintype "input"))
    )
    (net (code "52") (name "Net-(IC8C-B)") (class "Default")
      (node (ref "C15") (pin "1") (pinfunction "1_1") (pintype "passive"))
      (node (ref "IC8") (pin "9") (pinfunction "B_9") (pintype "tri_state"))
      (node (ref "R25") (pin "2") (pinfunction "2_2") (pintype "passive"))
    )
    (net (code "53") (name "Net-(IC9A--IN)") (class "Default")
      (node (ref "C22") (pin "1") (pinfunction "1_1") (pintype "passive"))
      (node (ref "IC9") (pin "2") (pinfunction "-IN_2") (pintype "input"))
      (node (ref "R26") (pin "1") (pinfunction "1_1") (pintype "passive"))
      (node (ref "R28") (pin "2") (pinfunction "2_2") (pintype "passive"))
    )
    (net (code "54") (name "Net-(IC9A-OUT)") (class "Default")
      (node (ref "C22") (pin "2") (pinfunction "2_2") (pintype "passive"))
      (node (ref "IC9") (pin "1") (pinfunction "OUT_1") (pintype "output"))
      (node (ref "R28") (pin "1") (pinfunction "1_1") (pintype "passive"))
      (node (ref "R30") (pin "3") (pinfunction "E_3") (pintype "passive"))
      (node (ref "TP10") (pin "TP") (pinfunction "TP_TP") (pintype "input"))
    )
    (net (code "55") (name "Net-(IC9B--IN)") (class "Default")
      (node (ref "C23") (pin "1") (pinfunction "1_1") (pintype "passive"))
      (node (ref "IC9") (pin "6") (pinfunction "-IN_6") (pintype "input"))
      (node (ref "R27") (pin "1") (pinfunction "1_1") (pintype "passive"))
      (node (ref "R29") (pin "2") (pinfunction "2_2") (pintype "passive"))
    )
    (net (code "56") (name "Net-(IC9C-V+)") (class "Default")
      (node (ref "C28") (pin "+") (pinfunction "+_+") (pintype "passive"))
      (node (ref "C29") (pin "2") (pinfunction "2_2") (pintype "passive"))
      (node (ref "IC9") (pin "8") (pinfunction "V+_8") (pintype "power_in"))
      (node (ref "L1") (pin "2") (pinfunction "2_2") (pintype "passive"))
    )
    (net (code "57") (name "Net-(LED1-PadA)") (class "Default")
      (node (ref "LED1") (pin "A") (pinfunction "A_A") (pintype "passive"))
      (node (ref "R32") (pin "1") (pinfunction "1_1") (pintype "passive"))
    )
    (net (code "58") (name "Net-(R30-A)") (class "Default")
      (node (ref "R30") (pin "1") (pinfunction "A_1") (pintype "passive"))
      (node (ref "R31") (pin "1") (pinfunction "1_1") (pintype "passive"))
    )
    (net (code "59") (name "Net-(TX/RX_COILE-S)") (class "Default")
      (node (ref "R10") (pin "2") (pinfunction "2_2") (pintype "passive"))
      (node (ref "R11") (pin "2") (pinfunction "2_2") (pintype "passive"))
      (node (ref "TP1") (pin "TP") (pinfunction "TP_TP") (pintype "input"))
      (node (ref "TX/RX_COIL") (pin "5") (pinfunction "S_5") (pintype "passive"))
    )
    (net (code "60") (name "unconnected-(ESP32-IO4-Pad26)") (class "Default")
      (node (ref "ESP32") (pin "26") (pinfunction "IO4_26") (pintype "bidirectional"))
    )
    (net (code "61") (name "unconnected-(ESP32-IO5-Pad29)") (class "Default")
      (node (ref "ESP32") (pin "29") (pinfunction "IO5_29") (pintype "bidirectional"))
    )
    (net (code "62") (name "unconnected-(ESP32-IO12-Pad14)") (class "Default")
      (node (ref "ESP32") (pin "14") (pinfunction "IO12_14") (pintype "bidirectional"))
    )
    (net (code "63") (name "unconnected-(ESP32-IO13-Pad16)") (class "Default")
      (node (ref "ESP32") (pin "16") (pinfunction "IO13_16") (pintype "bidirectional"))
    )
    (net (code "64") (name "unconnected-(ESP32-IO14-Pad13)") (class "Default")
      (node (ref "ESP32") (pin "13") (pinfunction "IO14_13") (pintype "bidirectional"))
    )
    (net (code "65") (name "unconnected-(ESP32-IO15-Pad23)") (class "Default")
      (node (ref "ESP32") (pin "23") (pinfunction "IO15_23") (pintype "bidirectional"))
    )
    (net (code "66") (name "unconnected-(ESP32-IO16-Pad27)") (class "Default")
      (node (ref "ESP32") (pin "27") (pinfunction "IO16_27") (pintype "bidirectional"))
    )
    (net (code "67") (name "unconnected-(ESP32-IO17-Pad28)") (class "Default")
      (node (ref "ESP32") (pin "28") (pinfunction "IO17_28") (pintype "bidirectional"))
    )
    (net (code "68") (name "unconnected-(ESP32-IO18-Pad30)") (class "Default")
      (node (ref "ESP32") (pin "30") (pinfunction "IO18_30") (pintype "bidirectional"))
    )
    (net (code "69") (name "unconnected-(ESP32-IO19-Pad31)") (class "Default")
      (node (ref "ESP32") (pin "31") (pinfunction "IO19_31") (pintype "bidirectional"))
    )
    (net (code "70") (name "unconnected-(ESP32-IO21-Pad33)") (class "Default")
      (node (ref "ESP32") (pin "33") (pinfunction "IO21_33") (pintype "bidirectional"))
    )
    (net (code "71") (name "unconnected-(ESP32-IO22-Pad36)") (class "Default")
      (node (ref "ESP32") (pin "36") (pinfunction "IO22_36") (pintype "bidirectional"))
    )
    (net (code "72") (name "unconnected-(ESP32-IO23-Pad37)") (class "Default")
      (node (ref "ESP32") (pin "37") (pinfunction "IO23_37") (pintype "bidirectional"))
    )
    (net (code "73") (name "unconnected-(ESP32-SCK-Pad20)") (class "Default")
      (node (ref "ESP32") (pin "20") (pinfunction "SCK_20") (pintype "bidirectional"))
    )
    (net (code "74") (name "unconnected-(ESP32-SCS-Pad19)") (class "Default")
      (node (ref "ESP32") (pin "19") (pinfunction "SCS_19") (pintype "bidirectional"))
    )
    (net (code "75") (name "unconnected-(ESP32-SDI-Pad22)") (class "Default")
      (node (ref "ESP32") (pin "22") (pinfunction "SDI_22") (pintype "bidirectional"))
    )
    (net (code "76") (name "unconnected-(ESP32-SDO-Pad21)") (class "Default")
      (node (ref "ESP32") (pin "21") (pinfunction "SDO_21") (pintype "bidirectional"))
    )
    (net (code "77") (name "unconnected-(ESP32-SHD-Pad17)") (class "Default")
      (node (ref "ESP32") (pin "17") (pinfunction "SHD_17") (pintype "bidirectional"))
    )
    (net (code "78") (name "unconnected-(ESP32-SWP-Pad18)") (class "Default")
      (node (ref "ESP32") (pin "18") (pinfunction "SWP_18") (pintype "bidirectional"))
    )
    (net (code "79") (name "unconnected-(IC8D-A-Pad11)") (class "Default")
      (node (ref "IC8") (pin "11") (pinfunction "A_11") (pintype "tri_state"))
    )
    (net (code "80") (name "unconnected-(IC8D-B-Pad10)") (class "Default")
      (node (ref "IC8") (pin "10") (pinfunction "B_10") (pintype "tri_state"))
    )
  )
)
